# MODULIQ_PGA.net
KiCad netlist of a schematic drawn in Altium Designer
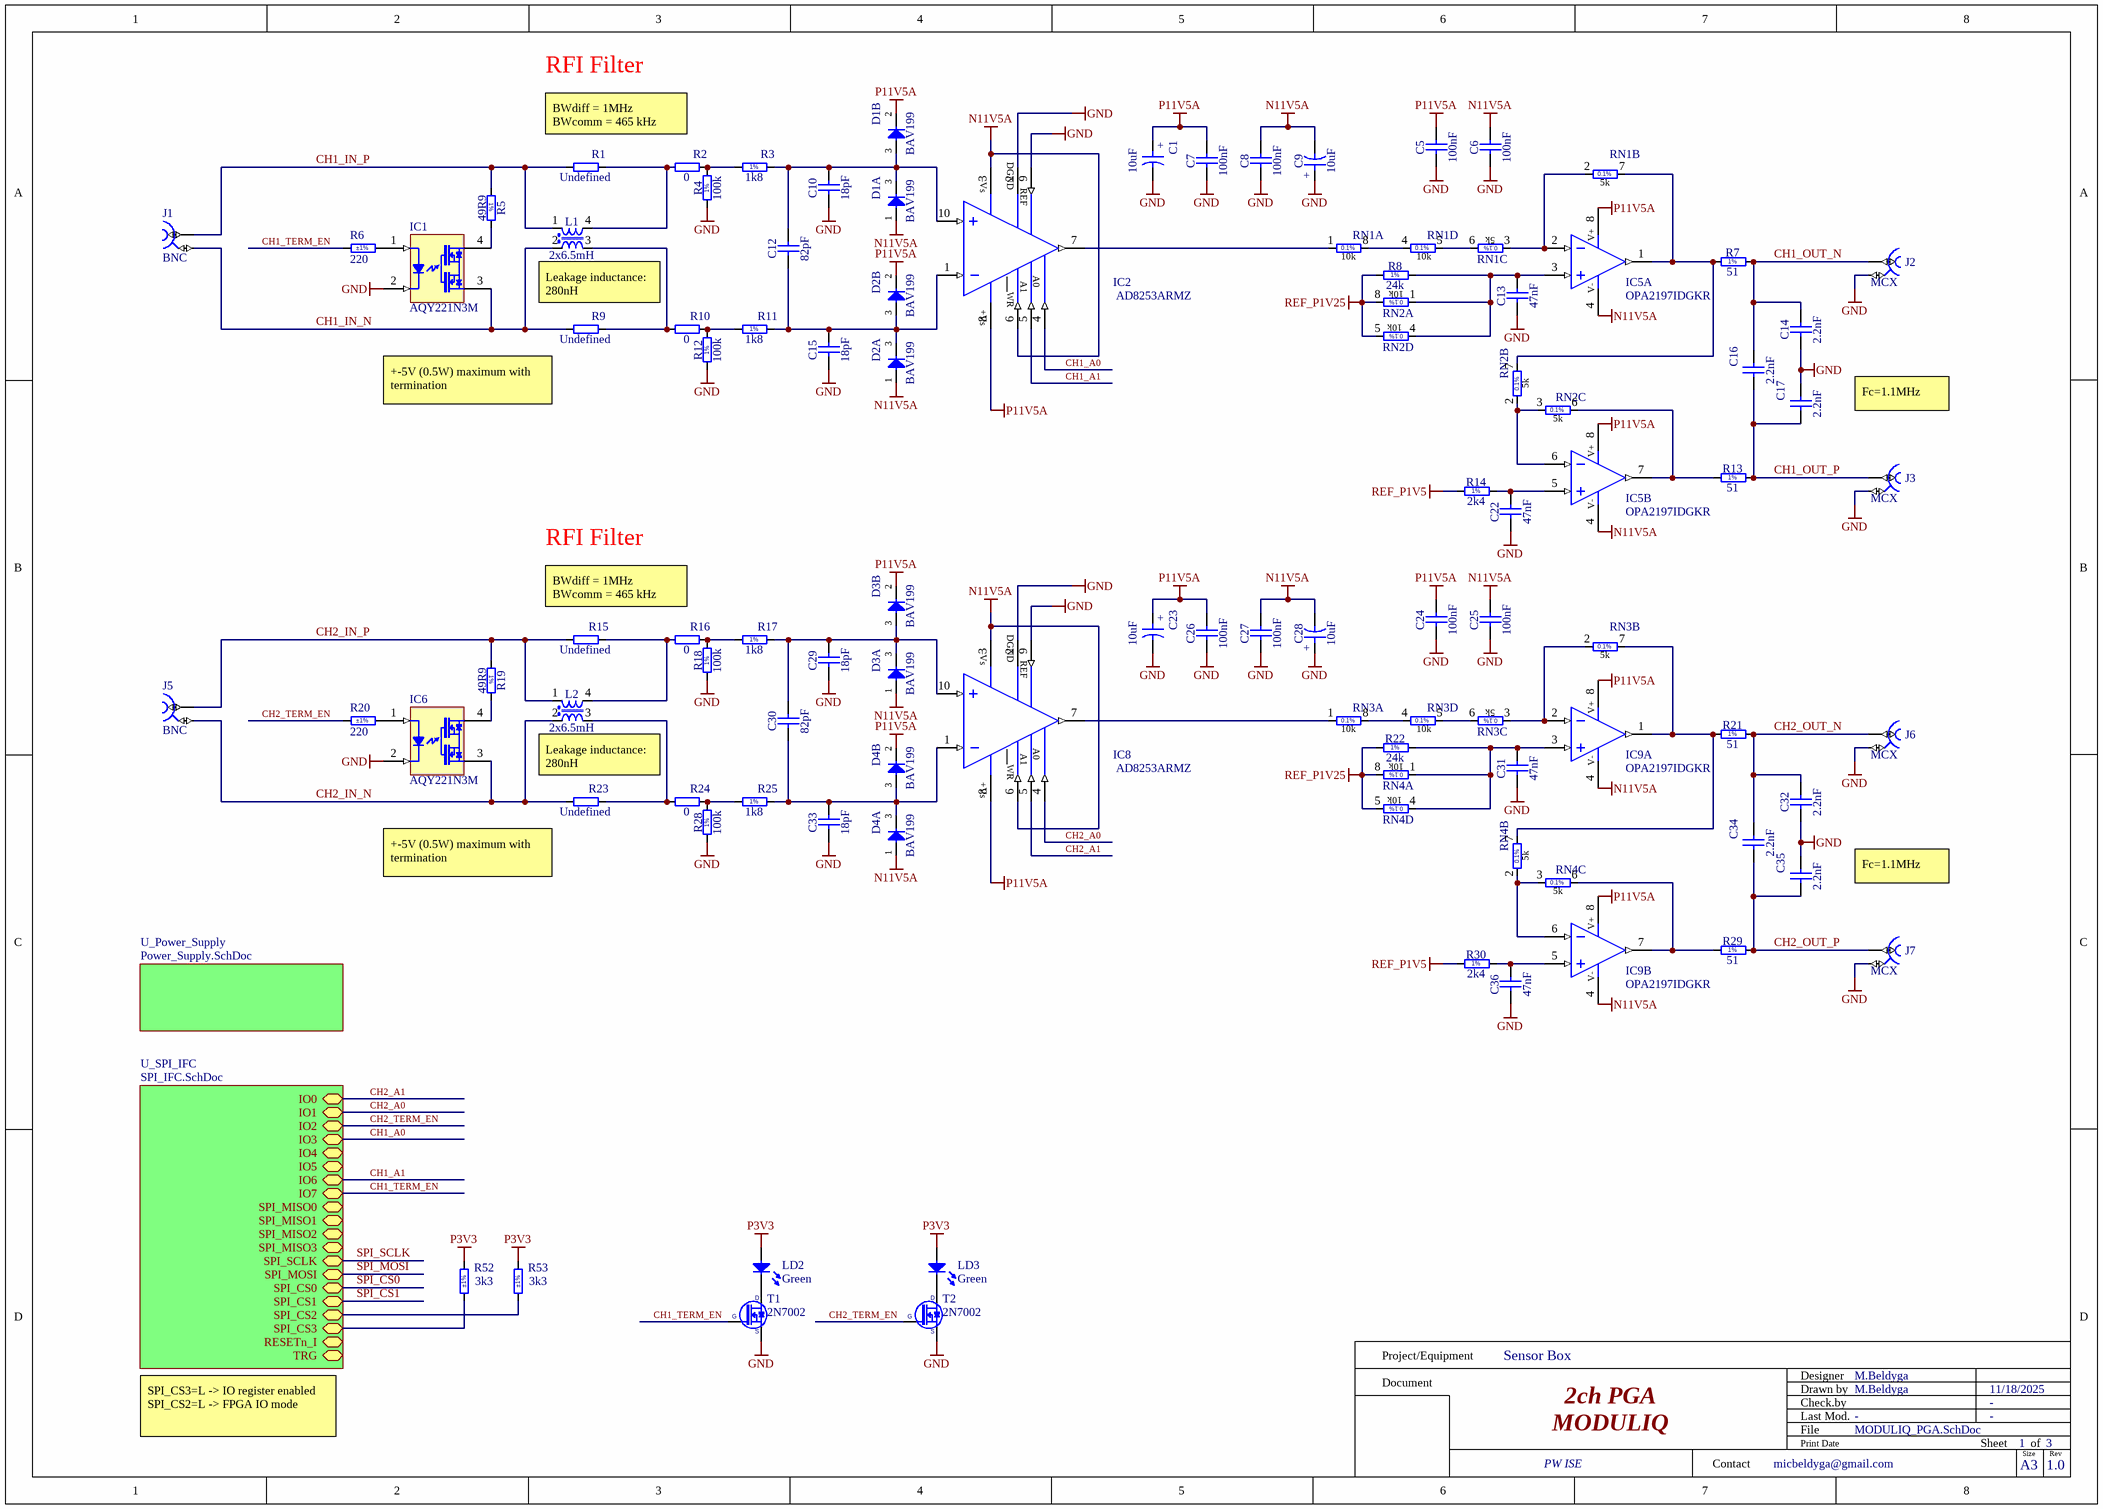
[diagram p0: MODULIQ_PGA.SchDoc]

(export (version "E")
  (design (tool "Eeschema 10.0.6"))
  (components
    (comp (ref "C1")
      (value "10uF")
      (footprint "CAPMP3216X180N")
      (description "Polarised capacitor")
      (fields
        (field (name "PART NUMBER") "CTE3216-18_10UF_16V_20%_AVX_TCJ")
        (field (name "VOLTAGE") "16V")
        (field (name "AUTHOR") "CERN DEM JLC")
      )
      (libsource (lib "Capacitors") (part "Capacitor - polarized"))
    )
    (comp (ref "C5")
      (value "100nF")
      (footprint "CAPC1005X55N")
      (description "Non-polarised capacitor")
      (fields
        (field (name "PART NUMBER") "CC0402_100NF_50V_10%_X7R")
        (field (name "VOLTAGE") "50V")
        (field (name "AUTHOR") "CERN DEM MR")
      )
      (libsource (lib "Capacitors") (part "Capacitor - non polarized"))
    )
    (comp (ref "C6")
      (value "100nF")
      (footprint "CAPC1005X55N")
      (description "Non-polarised capacitor")
      (fields
        (field (name "PART NUMBER") "CC0402_100NF_50V_10%_X7R")
        (field (name "VOLTAGE") "50V")
        (field (name "AUTHOR") "CERN DEM MR")
      )
      (libsource (lib "Capacitors") (part "Capacitor - non polarized"))
    )
    (comp (ref "C7")
      (value "100nF")
      (footprint "CAPC1005X55N")
      (description "Non-polarised capacitor")
      (fields
        (field (name "PART NUMBER") "CC0402_100NF_50V_10%_X7R")
        (field (name "VOLTAGE") "50V")
        (field (name "AUTHOR") "CERN DEM MR")
      )
      (libsource (lib "Capacitors") (part "Capacitor - non polarized"))
    )
    (comp (ref "C8")
      (value "100nF")
      (footprint "CAPC1005X55N")
      (description "Non-polarised capacitor")
      (fields
        (field (name "PART NUMBER") "CC0402_100NF_50V_10%_X7R")
        (field (name "VOLTAGE") "50V")
        (field (name "AUTHOR") "CERN DEM MR")
      )
      (libsource (lib "Capacitors") (part "Capacitor - non polarized"))
    )
    (comp (ref "C9")
      (value "10uF")
      (footprint "CAPMP3216X180N")
      (description "Polarised capacitor")
      (fields
        (field (name "PART NUMBER") "CTE3216-18_10UF_16V_20%_AVX_TCJ")
        (field (name "VOLTAGE") "16V")
        (field (name "AUTHOR") "CERN DEM JLC")
      )
      (libsource (lib "Capacitors") (part "Capacitor - polarized"))
    )
    (comp (ref "C10")
      (value "18pF")
      (footprint "CAPC1608X87N")
      (description "Non-polarised capacitor")
      (fields
        (field (name "PART NUMBER") "CC0603_18PF_50V_5%_NP0")
        (field (name "VOLTAGE") "50V")
        (field (name "AUTHOR") "CERN DEM JLC")
      )
      (libsource (lib "Capacitors") (part "Capacitor - non polarized"))
    )
    (comp (ref "C12")
      (value "82pF")
      (footprint "CAPC2012X90N")
      (description "Non-polarised capacitor")
      (fields
        (field (name "PART NUMBER") "CC0805_82PF_100V_1%_NP0_AVX_08051A820FAT2A")
        (field (name "VOLTAGE") "100V")
        (field (name "AUTHOR") "CERN DEM WB")
      )
      (libsource (lib "Capacitors") (part "Capacitor - non polarized"))
    )
    (comp (ref "C13")
      (value "47nF")
      (footprint "CAPC2012X135N")
      (description "Non-polarised capacitor")
      (fields
        (field (name "PART NUMBER") "CC0805_47NF_25V_5%_C0G")
        (field (name "VOLTAGE") "25V")
        (field (name "AUTHOR") "CERN DEM JLC")
      )
      (libsource (lib "Capacitors") (part "Capacitor - non polarized"))
    )
    (comp (ref "C14")
      (value "2.2nF")
      (footprint "CAPC2013X100N")
      (description "Non-polarised capacitor")
      (fields
        (field (name "PART NUMBER") "CC0805_2.2NF_25V_1%_C0G")
        (field (name "VOLTAGE") "25V")
        (field (name "AUTHOR") "CERN DEM JLC")
      )
      (libsource (lib "Capacitors") (part "Capacitor - non polarized"))
    )
    (comp (ref "C15")
      (value "18pF")
      (footprint "CAPC1608X87N")
      (description "Non-polarised capacitor")
      (fields
        (field (name "PART NUMBER") "CC0603_18PF_50V_5%_NP0")
        (field (name "VOLTAGE") "50V")
        (field (name "AUTHOR") "CERN DEM JLC")
      )
      (libsource (lib "Capacitors") (part "Capacitor - non polarized"))
    )
    (comp (ref "C16")
      (value "2.2nF")
      (footprint "CAPC2013X100N")
      (description "Non-polarised capacitor")
      (fields
        (field (name "PART NUMBER") "CC0805_2.2NF_25V_1%_C0G")
        (field (name "VOLTAGE") "25V")
        (field (name "AUTHOR") "CERN DEM JLC")
      )
      (libsource (lib "Capacitors") (part "Capacitor - non polarized"))
    )
    (comp (ref "C17")
      (value "2.2nF")
      (footprint "CAPC2013X100N")
      (description "Non-polarised capacitor")
      (fields
        (field (name "PART NUMBER") "CC0805_2.2NF_25V_1%_C0G")
        (field (name "VOLTAGE") "25V")
        (field (name "AUTHOR") "CERN DEM JLC")
      )
      (libsource (lib "Capacitors") (part "Capacitor - non polarized"))
    )
    (comp (ref "C22")
      (value "47nF")
      (footprint "CAPC2012X135N")
      (description "Non-polarised capacitor")
      (fields
        (field (name "PART NUMBER") "CC0805_47NF_25V_5%_C0G")
        (field (name "VOLTAGE") "25V")
        (field (name "AUTHOR") "CERN DEM JLC")
      )
      (libsource (lib "Capacitors") (part "Capacitor - non polarized"))
    )
    (comp (ref "C23")
      (value "10uF")
      (footprint "CAPMP3216X180N")
      (description "Polarised capacitor")
      (fields
        (field (name "PART NUMBER") "CTE3216-18_10UF_16V_20%_AVX_TCJ")
        (field (name "VOLTAGE") "16V")
        (field (name "AUTHOR") "CERN DEM JLC")
      )
      (libsource (lib "Capacitors") (part "Capacitor - polarized"))
    )
    (comp (ref "C24")
      (value "100nF")
      (footprint "CAPC1005X55N")
      (description "Non-polarised capacitor")
      (fields
        (field (name "PART NUMBER") "CC0402_100NF_50V_10%_X7R")
        (field (name "VOLTAGE") "50V")
        (field (name "AUTHOR") "CERN DEM MR")
      )
      (libsource (lib "Capacitors") (part "Capacitor - non polarized"))
    )
    (comp (ref "C25")
      (value "100nF")
      (footprint "CAPC1005X55N")
      (description "Non-polarised capacitor")
      (fields
        (field (name "PART NUMBER") "CC0402_100NF_50V_10%_X7R")
        (field (name "VOLTAGE") "50V")
        (field (name "AUTHOR") "CERN DEM MR")
      )
      (libsource (lib "Capacitors") (part "Capacitor - non polarized"))
    )
    (comp (ref "C26")
      (value "100nF")
      (footprint "CAPC1005X55N")
      (description "Non-polarised capacitor")
      (fields
        (field (name "PART NUMBER") "CC0402_100NF_50V_10%_X7R")
        (field (name "VOLTAGE") "50V")
        (field (name "AUTHOR") "CERN DEM MR")
      )
      (libsource (lib "Capacitors") (part "Capacitor - non polarized"))
    )
    (comp (ref "C27")
      (value "100nF")
      (footprint "CAPC1005X55N")
      (description "Non-polarised capacitor")
      (fields
        (field (name "PART NUMBER") "CC0402_100NF_50V_10%_X7R")
        (field (name "VOLTAGE") "50V")
        (field (name "AUTHOR") "CERN DEM MR")
      )
      (libsource (lib "Capacitors") (part "Capacitor - non polarized"))
    )
    (comp (ref "C28")
      (value "10uF")
      (footprint "CAPMP3216X180N")
      (description "Polarised capacitor")
      (fields
        (field (name "PART NUMBER") "CTE3216-18_10UF_16V_20%_AVX_TCJ")
        (field (name "VOLTAGE") "16V")
        (field (name "AUTHOR") "CERN DEM JLC")
      )
      (libsource (lib "Capacitors") (part "Capacitor - polarized"))
    )
    (comp (ref "C29")
      (value "18pF")
      (footprint "CAPC1608X87N")
      (description "Non-polarised capacitor")
      (fields
        (field (name "PART NUMBER") "CC0603_18PF_50V_5%_NP0")
        (field (name "VOLTAGE") "50V")
        (field (name "AUTHOR") "CERN DEM JLC")
      )
      (libsource (lib "Capacitors") (part "Capacitor - non polarized"))
    )
    (comp (ref "C30")
      (value "82pF")
      (footprint "CAPC2012X90N")
      (description "Non-polarised capacitor")
      (fields
        (field (name "PART NUMBER") "CC0805_82PF_100V_1%_NP0_AVX_08051A820FAT2A")
        (field (name "VOLTAGE") "100V")
        (field (name "AUTHOR") "CERN DEM WB")
      )
      (libsource (lib "Capacitors") (part "Capacitor - non polarized"))
    )
    (comp (ref "C31")
      (value "47nF")
      (footprint "CAPC2012X135N")
      (description "Non-polarised capacitor")
      (fields
        (field (name "PART NUMBER") "CC0805_47NF_25V_5%_C0G")
        (field (name "VOLTAGE") "25V")
        (field (name "AUTHOR") "CERN DEM JLC")
      )
      (libsource (lib "Capacitors") (part "Capacitor - non polarized"))
    )
    (comp (ref "C32")
      (value "2.2nF")
      (footprint "CAPC2013X100N")
      (description "Non-polarised capacitor")
      (fields
        (field (name "PART NUMBER") "CC0805_2.2NF_25V_1%_C0G")
        (field (name "VOLTAGE") "25V")
        (field (name "AUTHOR") "CERN DEM JLC")
      )
      (libsource (lib "Capacitors") (part "Capacitor - non polarized"))
    )
    (comp (ref "C33")
      (value "18pF")
      (footprint "CAPC1608X87N")
      (description "Non-polarised capacitor")
      (fields
        (field (name "PART NUMBER") "CC0603_18PF_50V_5%_NP0")
        (field (name "VOLTAGE") "50V")
        (field (name "AUTHOR") "CERN DEM JLC")
      )
      (libsource (lib "Capacitors") (part "Capacitor - non polarized"))
    )
    (comp (ref "C34")
      (value "2.2nF")
      (footprint "CAPC2013X100N")
      (description "Non-polarised capacitor")
      (fields
        (field (name "PART NUMBER") "CC0805_2.2NF_25V_1%_C0G")
        (field (name "VOLTAGE") "25V")
        (field (name "AUTHOR") "CERN DEM JLC")
      )
      (libsource (lib "Capacitors") (part "Capacitor - non polarized"))
    )
    (comp (ref "C35")
      (value "2.2nF")
      (footprint "CAPC2013X100N")
      (description "Non-polarised capacitor")
      (fields
        (field (name "PART NUMBER") "CC0805_2.2NF_25V_1%_C0G")
        (field (name "VOLTAGE") "25V")
        (field (name "AUTHOR") "CERN DEM JLC")
      )
      (libsource (lib "Capacitors") (part "Capacitor - non polarized"))
    )
    (comp (ref "C36")
      (value "47nF")
      (footprint "CAPC2012X135N")
      (description "Non-polarised capacitor")
      (fields
        (field (name "PART NUMBER") "CC0805_47NF_25V_5%_C0G")
        (field (name "VOLTAGE") "25V")
        (field (name "AUTHOR") "CERN DEM JLC")
      )
      (libsource (lib "Capacitors") (part "Capacitor - non polarized"))
    )
    (comp (ref "D1")
      (value "BAV199")
      (footprint "SOT95P240X110-3N")
      (description "Serial Diode")
      (fields
        (field (name "VOLTAGE") "75V")
        (field (name "POWER") "250mW")
        (field (name "AUTHOR") "CERN DEM JMW")
      )
      (libsource (lib "ICs And Semiconductors") (part "Diode x2 A1C3_A3C2"))
    )
    (comp (ref "D2")
      (value "BAV199")
      (footprint "SOT95P240X110-3N")
      (description "Serial Diode")
      (fields
        (field (name "VOLTAGE") "75V")
        (field (name "POWER") "250mW")
        (field (name "AUTHOR") "CERN DEM JMW")
      )
      (libsource (lib "ICs And Semiconductors") (part "Diode x2 A1C3_A3C2"))
    )
    (comp (ref "D3")
      (value "BAV199")
      (footprint "SOT95P240X110-3N")
      (description "Serial Diode")
      (fields
        (field (name "VOLTAGE") "75V")
        (field (name "POWER") "250mW")
        (field (name "AUTHOR") "CERN DEM JMW")
      )
      (libsource (lib "ICs And Semiconductors") (part "Diode x2 A1C3_A3C2"))
    )
    (comp (ref "D4")
      (value "BAV199")
      (footprint "SOT95P240X110-3N")
      (description "Serial Diode")
      (fields
        (field (name "VOLTAGE") "75V")
        (field (name "POWER") "250mW")
        (field (name "AUTHOR") "CERN DEM JMW")
      )
      (libsource (lib "ICs And Semiconductors") (part "Diode x2 A1C3_A3C2"))
    )
    (comp (ref "IC1")
      (value "AQY221N3M")
      (footprint "PANASONIC_AQY22(SON)")
      (description "PhotoMOS Relay")
      (fields (field (name "MANUFACTURER") "PANASONIC") (field (name "AUTHOR") "CERN DEM JLC"))
      (libsource (lib "ICs And Semiconductors") (part "PhotoMOS Relay x1 Type5_a"))
    )
    (comp (ref "IC2")
      (value "AD8253ARMZ")
      (footprint "SOP50P490X110-10N")
      (description "10MHz, 20V/us, G= 1, 10, 100, 1000 iCMOS Programmable Gain Instrumentation Amplifier")
      (fields (field (name "MANUFACTURER") "ANALOG DEVICES") (field (name "AUTHOR") "CERN DEM JLC"))
      (libsource (lib "ICs And Semiconductors") (part "AD8253"))
    )
    (comp (ref "IC5")
      (value "OPA2197IDGKR")
      (footprint "SOP65P490X110-8N")
      (description "36-V, Precision, Rail-to-Rail Input Output, Low Offset Voltage Op Amp 8-VSSOP")
      (fields (field (name "MANUFACTURER") "TEXAS INSTRUMENTS") (field (name "AUTHOR") "GK"))
      (libsource (lib "LIBRARY_SCH") (part "OA_OPA2197IDGKR"))
    )
    (comp (ref "IC6")
      (value "AQY221N3M")
      (footprint "PANASONIC_AQY22(SON)")
      (description "PhotoMOS Relay")
      (fields (field (name "MANUFACTURER") "PANASONIC") (field (name "AUTHOR") "CERN DEM JLC"))
      (libsource (lib "ICs And Semiconductors") (part "PhotoMOS Relay x1 Type5_a"))
    )
    (comp (ref "IC8")
      (value "AD8253ARMZ")
      (footprint "SOP50P490X110-10N")
      (description "10MHz, 20V/us, G= 1, 10, 100, 1000 iCMOS Programmable Gain Instrumentation Amplifier")
      (fields (field (name "MANUFACTURER") "ANALOG DEVICES") (field (name "AUTHOR") "CERN DEM JLC"))
      (libsource (lib "ICs And Semiconductors") (part "AD8253"))
    )
    (comp (ref "IC9")
      (value "OPA2197IDGKR")
      (footprint "SOP65P490X110-8N")
      (description "36-V, Precision, Rail-to-Rail Input Output, Low Offset Voltage Op Amp 8-VSSOP")
      (fields (field (name "MANUFACTURER") "TEXAS INSTRUMENTS") (field (name "AUTHOR") "GK"))
      (libsource (lib "LIBRARY_SCH") (part "OA_OPA2197IDGKR"))
    )
    (comp (ref "J1")
      (value "BNC")
      (footprint "AMPHENOL_112515")
      (fields
        (field (name "PART NUMBER") "AMPHENOL_112515")
        (field (name "MANUFACTURER") "AMPHENOL-RF")
        (field (name "MANUFACTURER PART NUMBER") "112515")
        (field (name "AUTHOR") "CERN DEM HF")
      )
      (libsource (lib "Connectors") (part "Coax_1Female_1Shield"))
    )
    (comp (ref "J2")
      (value "MCX")
      (footprint "AMPHENOL_919-109J-51PX")
      (fields
        (field (name "PART NUMBER") "AMPHENOL_919-109J-51PX")
        (field (name "MANUFACTURER") "AMPHENOL")
        (field (name "MANUFACTURER PART NUMBER") "919-109J-51PX (MCX6251B1-3GT30G-50)")
        (field (name "AUTHOR") "CERN DEM BC")
      )
      (libsource (lib "") (part "Coax_1Female_1Shield_1"))
    )
    (comp (ref "J3")
      (value "MCX")
      (footprint "AMPHENOL_919-109J-51PX")
      (fields
        (field (name "PART NUMBER") "AMPHENOL_919-109J-51PX")
        (field (name "MANUFACTURER") "AMPHENOL")
        (field (name "MANUFACTURER PART NUMBER") "919-109J-51PX (MCX6251B1-3GT30G-50)")
        (field (name "AUTHOR") "CERN DEM BC")
      )
      (libsource (lib "") (part "Coax_1Female_1Shield_1"))
    )
    (comp (ref "J5")
      (value "BNC")
      (footprint "AMPHENOL_112515")
      (fields
        (field (name "PART NUMBER") "AMPHENOL_112515")
        (field (name "MANUFACTURER") "AMPHENOL-RF")
        (field (name "MANUFACTURER PART NUMBER") "112515")
        (field (name "AUTHOR") "CERN DEM HF")
      )
      (libsource (lib "Connectors") (part "Coax_1Female_1Shield"))
    )
    (comp (ref "J6")
      (value "MCX")
      (footprint "AMPHENOL_919-109J-51PX")
      (fields
        (field (name "PART NUMBER") "AMPHENOL_919-109J-51PX")
        (field (name "MANUFACTURER") "AMPHENOL")
        (field (name "MANUFACTURER PART NUMBER") "919-109J-51PX (MCX6251B1-3GT30G-50)")
        (field (name "AUTHOR") "CERN DEM BC")
      )
      (libsource (lib "") (part "Coax_1Female_1Shield_1"))
    )
    (comp (ref "J7")
      (value "MCX")
      (footprint "AMPHENOL_919-109J-51PX")
      (fields
        (field (name "PART NUMBER") "AMPHENOL_919-109J-51PX")
        (field (name "MANUFACTURER") "AMPHENOL")
        (field (name "MANUFACTURER PART NUMBER") "919-109J-51PX (MCX6251B1-3GT30G-50)")
        (field (name "AUTHOR") "CERN DEM BC")
      )
      (libsource (lib "") (part "Coax_1Female_1Shield_1"))
    )
    (comp (ref "L1")
      (value "2x6.5mH")
      (footprint "IND_WURTH_WE-SL2")
      (description "Inductor Common Mode")
      (fields
        (field (name "PART NUMBER") "IND_6.5MH_50%_WURTH_WE-SL2-744229")
        (field (name "POWER") "400mA")
        (field (name "AUTHOR") "CERN DEM JLC")
      )
      (libsource (lib "Inductors & Transformers") (part "Inductor Common Mode 1Dot-4 2Dot-3"))
    )
    (comp (ref "L2")
      (value "2x6.5mH")
      (footprint "IND_WURTH_WE-SL2")
      (description "Inductor Common Mode")
      (fields
        (field (name "PART NUMBER") "IND_6.5MH_50%_WURTH_WE-SL2-744229")
        (field (name "POWER") "400mA")
        (field (name "AUTHOR") "CERN DEM JLC")
      )
      (libsource (lib "Inductors & Transformers") (part "Inductor Common Mode 1Dot-4 2Dot-3"))
    )
    (comp (ref "LD2")
      (value "Green")
      (footprint "LED_KINGBRIGHT_KP-1608CGCK")
      (description "LED Green 1C 2A")
      (fields
        (field (name "PART NUMBER") "LED_KINGBRIGHT_KP-1608CGCK")
        (field (name "MANUFACTURER") "KINGBRIGHT")
        (field (name "AUTHOR") "CERN DEM HF")
      )
      (libsource (lib "ICs And Semiconductors") (part "LED Green 1C 2A"))
    )
    (comp (ref "LD3")
      (value "Green")
      (footprint "LED_KINGBRIGHT_KP-1608CGCK")
      (description "LED Green 1C 2A")
      (fields
        (field (name "PART NUMBER") "LED_KINGBRIGHT_KP-1608CGCK")
        (field (name "MANUFACTURER") "KINGBRIGHT")
        (field (name "AUTHOR") "CERN DEM HF")
      )
      (libsource (lib "ICs And Semiconductors") (part "LED Green 1C 2A"))
    )
    (comp (ref "R1")
      (value "Undefined")
      (footprint "RESC1608X55N")
      (description "Resistor")
      (fields (field (name "PART NUMBER") "R0603_NO-VALUE") (field (name "AUTHOR") "CERN DEM JLC"))
      (libsource (lib "Resistors") (part "Resistor"))
    )
    (comp (ref "R2")
      (value "0")
      (footprint "RESC1608X55N")
      (description "Resistor")
      (fields
        (field (name "PART NUMBER") "R0603_0R_JUMPER")
        (field (name "MANUFACTURER") "GENERIC")
        (field (name "AUTHOR") "CERN DEM JLC")
      )
      (libsource (lib "Resistors") (part "Resistor"))
    )
    (comp (ref "R3")
      (value "1k8")
      (footprint "RESC1608X55N")
      (description "Resistor - 1%")
      (fields
        (field (name "PART NUMBER") "R0603_1K8_1%_0.1W_100PPM")
        (field (name "POWER") "0.1W")
        (field (name "AUTHOR") "CERN DEM JLC")
      )
      (libsource (lib "") (part "Resistor - 1%_1"))
    )
    (comp (ref "R4")
      (value "100k")
      (footprint "RESC1608X55N")
      (description "Resistor - 1%")
      (fields
        (field (name "PART NUMBER") "R0603_100K_1%_0.1W_100PPM")
        (field (name "POWER") "0.1W")
        (field (name "AUTHOR") "CERN DEM JLC")
      )
      (libsource (lib "") (part "Resistor - 1%_1"))
    )
    (comp (ref "R5")
      (value "49R9")
      (footprint "RESC6331X70N")
      (description "Resistor - 1%")
      (fields
        (field (name "PART NUMBER") "R2512_49R9_1%_1W_100PPM_VISHAY_CRCW")
        (field (name "POWER") "1W")
        (field (name "AUTHOR") "CERN DEM JLC")
      )
      (libsource (lib "") (part "Resistor - 1%_1"))
    )
    (comp (ref "R6")
      (value "220")
      (footprint "RESC1005X40N")
      (description "Resistor - 1%")
      (fields
        (field (name "TOLERANCE") "±1%")
        (field (name "PART NUMBER") "R0402_220R_1%_0.0625W_100PPM")
        (field (name "POWER") "0.0625W")
        (field (name "AUTHOR") "CERN DEM JLC")
      )
      (libsource (lib "Resistors") (part "Resistor - 1%"))
    )
    (comp (ref "R7")
      (value "51")
      (footprint "RESC1005X40N")
      (description "Resistor - 1%")
      (fields
        (field (name "PART NUMBER") "R0402_51R_1%_0.0625W_100PPM")
        (field (name "POWER") "0.0625W")
        (field (name "AUTHOR") "CERN DEM JLC")
      )
      (libsource (lib "Resistors") (part "Resistor - 1%"))
    )
    (comp (ref "R8")
      (value "24k")
      (footprint "RESC1608X55N")
      (description "Resistor - 1%")
      (fields
        (field (name "PART NUMBER") "R0603_24K_1%_0.1W_100PPM")
        (field (name "POWER") "0.1W")
        (field (name "AUTHOR") "CERN DEM JLC")
      )
      (libsource (lib "") (part "Resistor - 1%_1"))
    )
    (comp (ref "R9")
      (value "Undefined")
      (footprint "RESC1608X55N")
      (description "Resistor")
      (fields (field (name "PART NUMBER") "R0603_NO-VALUE") (field (name "AUTHOR") "CERN DEM JLC"))
      (libsource (lib "Resistors") (part "Resistor"))
    )
    (comp (ref "R10")
      (value "0")
      (footprint "RESC1608X55N")
      (description "Resistor")
      (fields
        (field (name "PART NUMBER") "R0603_0R_JUMPER")
        (field (name "MANUFACTURER") "GENERIC")
        (field (name "AUTHOR") "CERN DEM JLC")
      )
      (libsource (lib "Resistors") (part "Resistor"))
    )
    (comp (ref "R11")
      (value "1k8")
      (footprint "RESC1608X55N")
      (description "Resistor - 1%")
      (fields
        (field (name "PART NUMBER") "R0603_1K8_1%_0.1W_100PPM")
        (field (name "POWER") "0.1W")
        (field (name "AUTHOR") "CERN DEM JLC")
      )
      (libsource (lib "") (part "Resistor - 1%_1"))
    )
    (comp (ref "R12")
      (value "100k")
      (footprint "RESC1608X55N")
      (description "Resistor - 1%")
      (fields
        (field (name "PART NUMBER") "R0603_100K_1%_0.1W_100PPM")
        (field (name "POWER") "0.1W")
        (field (name "AUTHOR") "CERN DEM JLC")
      )
      (libsource (lib "") (part "Resistor - 1%_1"))
    )
    (comp (ref "R13")
      (value "51")
      (footprint "RESC1005X40N")
      (description "Resistor - 1%")
      (fields
        (field (name "PART NUMBER") "R0402_51R_1%_0.0625W_100PPM")
        (field (name "POWER") "0.0625W")
        (field (name "AUTHOR") "CERN DEM JLC")
      )
      (libsource (lib "Resistors") (part "Resistor - 1%"))
    )
    (comp (ref "R14")
      (value "2k4")
      (footprint "RESC1005X40N")
      (description "Resistor - 1%")
      (fields
        (field (name "PART NUMBER") "R0402_2K4_1%_0.0625W_100PPM")
        (field (name "POWER") "0.0625W")
        (field (name "AUTHOR") "CERN DEM JLC")
      )
      (libsource (lib "Resistors") (part "Resistor - 1%"))
    )
    (comp (ref "R15")
      (value "Undefined")
      (footprint "RESC1608X55N")
      (description "Resistor")
      (fields (field (name "PART NUMBER") "R0603_NO-VALUE") (field (name "AUTHOR") "CERN DEM JLC"))
      (libsource (lib "Resistors") (part "Resistor"))
    )
    (comp (ref "R16")
      (value "0")
      (footprint "RESC1608X55N")
      (description "Resistor")
      (fields
        (field (name "PART NUMBER") "R0603_0R_JUMPER")
        (field (name "MANUFACTURER") "GENERIC")
        (field (name "AUTHOR") "CERN DEM JLC")
      )
      (libsource (lib "Resistors") (part "Resistor"))
    )
    (comp (ref "R17")
      (value "1k8")
      (footprint "RESC1608X55N")
      (description "Resistor - 1%")
      (fields
        (field (name "PART NUMBER") "R0603_1K8_1%_0.1W_100PPM")
        (field (name "POWER") "0.1W")
        (field (name "AUTHOR") "CERN DEM JLC")
      )
      (libsource (lib "") (part "Resistor - 1%_1"))
    )
    (comp (ref "R18")
      (value "100k")
      (footprint "RESC1608X55N")
      (description "Resistor - 1%")
      (fields
        (field (name "PART NUMBER") "R0603_100K_1%_0.1W_100PPM")
        (field (name "POWER") "0.1W")
        (field (name "AUTHOR") "CERN DEM JLC")
      )
      (libsource (lib "") (part "Resistor - 1%_1"))
    )
    (comp (ref "R19")
      (value "49R9")
      (footprint "RESC6331X70N")
      (description "Resistor - 1%")
      (fields
        (field (name "PART NUMBER") "R2512_49R9_1%_1W_100PPM_VISHAY_CRCW")
        (field (name "POWER") "1W")
        (field (name "AUTHOR") "CERN DEM JLC")
      )
      (libsource (lib "") (part "Resistor - 1%_1"))
    )
    (comp (ref "R20")
      (value "220")
      (footprint "RESC1005X40N")
      (description "Resistor - 1%")
      (fields
        (field (name "TOLERANCE") "±1%")
        (field (name "PART NUMBER") "R0402_220R_1%_0.0625W_100PPM")
        (field (name "POWER") "0.0625W")
        (field (name "AUTHOR") "CERN DEM JLC")
      )
      (libsource (lib "Resistors") (part "Resistor - 1%"))
    )
    (comp (ref "R21")
      (value "51")
      (footprint "RESC1005X40N")
      (description "Resistor - 1%")
      (fields
        (field (name "PART NUMBER") "R0402_51R_1%_0.0625W_100PPM")
        (field (name "POWER") "0.0625W")
        (field (name "AUTHOR") "CERN DEM JLC")
      )
      (libsource (lib "Resistors") (part "Resistor - 1%"))
    )
    (comp (ref "R22")
      (value "24k")
      (footprint "RESC1608X55N")
      (description "Resistor - 1%")
      (fields
        (field (name "PART NUMBER") "R0603_24K_1%_0.1W_100PPM")
        (field (name "POWER") "0.1W")
        (field (name "AUTHOR") "CERN DEM JLC")
      )
      (libsource (lib "") (part "Resistor - 1%_1"))
    )
    (comp (ref "R23")
      (value "Undefined")
      (footprint "RESC1608X55N")
      (description "Resistor")
      (fields (field (name "PART NUMBER") "R0603_NO-VALUE") (field (name "AUTHOR") "CERN DEM JLC"))
      (libsource (lib "Resistors") (part "Resistor"))
    )
    (comp (ref "R24")
      (value "0")
      (footprint "RESC1608X55N")
      (description "Resistor")
      (fields
        (field (name "PART NUMBER") "R0603_0R_JUMPER")
        (field (name "MANUFACTURER") "GENERIC")
        (field (name "AUTHOR") "CERN DEM JLC")
      )
      (libsource (lib "Resistors") (part "Resistor"))
    )
    (comp (ref "R25")
      (value "1k8")
      (footprint "RESC1608X55N")
      (description "Resistor - 1%")
      (fields
        (field (name "PART NUMBER") "R0603_1K8_1%_0.1W_100PPM")
        (field (name "POWER") "0.1W")
        (field (name "AUTHOR") "CERN DEM JLC")
      )
      (libsource (lib "") (part "Resistor - 1%_1"))
    )
    (comp (ref "R28")
      (value "100k")
      (footprint "RESC1608X55N")
      (description "Resistor - 1%")
      (fields
        (field (name "PART NUMBER") "R0603_100K_1%_0.1W_100PPM")
        (field (name "POWER") "0.1W")
        (field (name "AUTHOR") "CERN DEM JLC")
      )
      (libsource (lib "") (part "Resistor - 1%_1"))
    )
    (comp (ref "R29")
      (value "51")
      (footprint "RESC1005X40N")
      (description "Resistor - 1%")
      (fields
        (field (name "PART NUMBER") "R0402_51R_1%_0.0625W_100PPM")
        (field (name "POWER") "0.0625W")
        (field (name "AUTHOR") "CERN DEM JLC")
      )
      (libsource (lib "Resistors") (part "Resistor - 1%"))
    )
    (comp (ref "R30")
      (value "2k4")
      (footprint "RESC1005X40N")
      (description "Resistor - 1%")
      (fields
        (field (name "PART NUMBER") "R0402_2K4_1%_0.0625W_100PPM")
        (field (name "POWER") "0.0625W")
        (field (name "AUTHOR") "CERN DEM JLC")
      )
      (libsource (lib "Resistors") (part "Resistor - 1%"))
    )
    (comp (ref "R52")
      (value "3k3")
      (footprint "RESC1005X40N")
      (description "Resistor - 1%")
      (fields
        (field (name "TOLERANCE") "±1%")
        (field (name "PART NUMBER") "R0402_3K3_1%_0.0625W_100PPM")
        (field (name "POWER") "0.0625W")
        (field (name "AUTHOR") "CERN DEM JLC")
      )
      (libsource (lib "Resistors") (part "Resistor - 1%"))
    )
    (comp (ref "R53")
      (value "3k3")
      (footprint "RESC1005X40N")
      (description "Resistor - 1%")
      (fields
        (field (name "TOLERANCE") "±1%")
        (field (name "PART NUMBER") "R0402_3K3_1%_0.0625W_100PPM")
        (field (name "POWER") "0.0625W")
        (field (name "AUTHOR") "CERN DEM JLC")
      )
      (libsource (lib "Resistors") (part "Resistor - 1%"))
    )
    (comp (ref "RN1")
      (value "10k 5K 5K 10K")
      (footprint "SOIC127P600X175-8N")
      (description "DIL8 Resistor Network 4 Resistors 10k-5k-5k-10k 0.1%")
      (fields
        (field (name "PART NUMBER") "RN_10K_5K_VISHAY_AORN2-1AT3")
        (field (name "POWER") "4x0.1W")
        (field (name "AUTHOR") "CERN DEM JLC")
      )
      (libsource (lib "Resistors") (part "RN DIL8_4xR_10k-5k-5k-10k_0.1%"))
    )
    (comp (ref "RN2")
      (value "10k 5K 5K 10K")
      (footprint "SOIC127P600X175-8N")
      (description "DIL8 Resistor Network 4 Resistors 10k-5k-5k-10k 0.1%")
      (fields
        (field (name "PART NUMBER") "RN_10K_5K_VISHAY_AORN2-1AT3")
        (field (name "POWER") "4x0.1W")
        (field (name "AUTHOR") "CERN DEM JLC")
      )
      (libsource (lib "Resistors") (part "RN DIL8_4xR_10k-5k-5k-10k_0.1%"))
    )
    (comp (ref "RN3")
      (value "10k 5K 5K 10K")
      (footprint "SOIC127P600X175-8N")
      (description "DIL8 Resistor Network 4 Resistors 10k-5k-5k-10k 0.1%")
      (fields
        (field (name "PART NUMBER") "RN_10K_5K_VISHAY_AORN2-1AT3")
        (field (name "POWER") "4x0.1W")
        (field (name "AUTHOR") "CERN DEM JLC")
      )
      (libsource (lib "Resistors") (part "RN DIL8_4xR_10k-5k-5k-10k_0.1%"))
    )
    (comp (ref "RN4")
      (value "10k 5K 5K 10K")
      (footprint "SOIC127P600X175-8N")
      (description "DIL8 Resistor Network 4 Resistors 10k-5k-5k-10k 0.1%")
      (fields
        (field (name "PART NUMBER") "RN_10K_5K_VISHAY_AORN2-1AT3")
        (field (name "POWER") "4x0.1W")
        (field (name "AUTHOR") "CERN DEM JLC")
      )
      (libsource (lib "Resistors") (part "RN DIL8_4xR_10k-5k-5k-10k_0.1%"))
    )
    (comp (ref "T1")
      (value "2N7002")
      (footprint "SOT95P240X130-3N")
      (description "N-CHANNEL MOSFET WITH DIODE")
      (fields (field (name "MANUFACTURER") "FAIRCHILD SEMICONDUCTOR") (field (name "AUTHOR") "CERN DEM JLC"))
      (libsource (lib "ICs And Semiconductors") (part "N-MOSFET-D 1G 2S 3D"))
    )
    (comp (ref "T2")
      (value "2N7002")
      (footprint "SOT95P240X130-3N")
      (description "N-CHANNEL MOSFET WITH DIODE")
      (fields (field (name "MANUFACTURER") "FAIRCHILD SEMICONDUCTOR") (field (name "AUTHOR") "CERN DEM JLC"))
      (libsource (lib "ICs And Semiconductors") (part "N-MOSFET-D 1G 2S 3D"))
    )
  )
  (nets
    (net (code "1") (name "/CH1_A0") (class "Default")
      (node (ref "IC2") (pin "4") (pinfunction "A0_4") (pintype "input"))
    )
    (net (code "2") (name "/CH1_A1") (class "Default")
      (node (ref "IC2") (pin "5") (pinfunction "A1_5") (pintype "input"))
    )
    (net (code "3") (name "/CH1_IN_N") (class "Default")
      (node (ref "IC1") (pin "3") (pinfunction "C_3") (pintype "open_collector"))
      (node (ref "J1") (pin "2") (pinfunction "2_2") (pintype "bidirectional"))
      (node (ref "L1") (pin "2") (pinfunction "2_2") (pintype "passive"))
      (node (ref "R9") (pin "1") (pinfunction "1_1") (pintype "passive"))
    )
    (net (code "4") (name "/CH1_IN_P") (class "Default")
      (node (ref "J1") (pin "1") (pinfunction "1_1") (pintype "bidirectional"))
      (node (ref "L1") (pin "1") (pinfunction "1_1") (pintype "passive"))
      (node (ref "R1") (pin "1") (pinfunction "1_1") (pintype "passive"))
      (node (ref "R5") (pin "1") (pinfunction "1_1") (pintype "passive"))
    )
    (net (code "5") (name "/CH1_OUT_N") (class "Default")
      (node (ref "C14") (pin "2") (pinfunction "2_2") (pintype "passive"))
      (node (ref "C16") (pin "2") (pinfunction "2_2") (pintype "passive"))
      (node (ref "J2") (pin "1") (pinfunction "1_1") (pintype "bidirectional"))
      (node (ref "R7") (pin "2") (pinfunction "2_2") (pintype "passive"))
    )
    (net (code "6") (name "/CH1_OUT_P") (class "Default")
      (node (ref "C16") (pin "1") (pinfunction "1_1") (pintype "passive"))
      (node (ref "C17") (pin "1") (pinfunction "1_1") (pintype "passive"))
      (node (ref "J3") (pin "1") (pinfunction "1_1") (pintype "bidirectional"))
      (node (ref "R13") (pin "2") (pinfunction "2_2") (pintype "passive"))
    )
    (net (code "7") (name "/CH1_TERM_EN") (class "Default")
      (node (ref "R6") (pin "1") (pinfunction "1_1") (pintype "passive"))
      (node (ref "T1") (pin "1") (pinfunction "G_1") (pintype "passive"))
    )
    (net (code "8") (name "/CH2_A0") (class "Default")
      (node (ref "IC8") (pin "4") (pinfunction "A0_4") (pintype "input"))
    )
    (net (code "9") (name "/CH2_A1") (class "Default")
      (node (ref "IC8") (pin "5") (pinfunction "A1_5") (pintype "input"))
    )
    (net (code "10") (name "/CH2_IN_N") (class "Default")
      (node (ref "IC6") (pin "3") (pinfunction "C_3") (pintype "open_collector"))
      (node (ref "J5") (pin "2") (pinfunction "2_2") (pintype "bidirectional"))
      (node (ref "L2") (pin "2") (pinfunction "2_2") (pintype "passive"))
      (node (ref "R23") (pin "1") (pinfunction "1_1") (pintype "passive"))
    )
    (net (code "11") (name "/CH2_IN_P") (class "Default")
      (node (ref "J5") (pin "1") (pinfunction "1_1") (pintype "bidirectional"))
      (node (ref "L2") (pin "1") (pinfunction "1_1") (pintype "passive"))
      (node (ref "R15") (pin "1") (pinfunction "1_1") (pintype "passive"))
      (node (ref "R19") (pin "1") (pinfunction "1_1") (pintype "passive"))
    )
    (net (code "12") (name "/CH2_OUT_N") (class "Default")
      (node (ref "C32") (pin "2") (pinfunction "2_2") (pintype "passive"))
      (node (ref "C34") (pin "2") (pinfunction "2_2") (pintype "passive"))
      (node (ref "J6") (pin "1") (pinfunction "1_1") (pintype "bidirectional"))
      (node (ref "R21") (pin "2") (pinfunction "2_2") (pintype "passive"))
    )
    (net (code "13") (name "/CH2_OUT_P") (class "Default")
      (node (ref "C34") (pin "1") (pinfunction "1_1") (pintype "passive"))
      (node (ref "C35") (pin "1") (pinfunction "1_1") (pintype "passive"))
      (node (ref "J7") (pin "1") (pinfunction "1_1") (pintype "bidirectional"))
      (node (ref "R29") (pin "2") (pinfunction "2_2") (pintype "passive"))
    )
    (net (code "14") (name "/CH2_TERM_EN") (class "Default")
      (node (ref "R20") (pin "1") (pinfunction "1_1") (pintype "passive"))
      (node (ref "T2") (pin "1") (pinfunction "G_1") (pintype "passive"))
    )
    (net (code "20") (name "/SPI_CS2") (class "Default")
      (node (ref "R53") (pin "2") (pinfunction "2_2") (pintype "passive"))
    )
    (net (code "21") (name "/SPI_CS3") (class "Default")
      (node (ref "R52") (pin "2") (pinfunction "2_2") (pintype "passive"))
    )
    (net (code "29") (name "GND") (class "Default")
      (node (ref "C1") (pin "2") (pinfunction "2_2") (pintype "passive"))
      (node (ref "C10") (pin "1") (pinfunction "1_1") (pintype "passive"))
      (node (ref "C13") (pin "1") (pinfunction "1_1") (pintype "passive"))
      (node (ref "C14") (pin "1") (pinfunction "1_1") (pintype "passive"))
      (node (ref "C15") (pin "1") (pinfunction "1_1") (pintype "passive"))
      (node (ref "C17") (pin "2") (pinfunction "2_2") (pintype "passive"))
      (node (ref "C22") (pin "1") (pinfunction "1_1") (pintype "passive"))
      (node (ref "C23") (pin "2") (pinfunction "2_2") (pintype "passive"))
      (node (ref "C24") (pin "1") (pinfunction "1_1") (pintype "passive"))
      (node (ref "C25") (pin "1") (pinfunction "1_1") (pintype "passive"))
      (node (ref "C26") (pin "1") (pinfunction "1_1") (pintype "passive"))
      (node (ref "C27") (pin "1") (pinfunction "1_1") (pintype "passive"))
      (node (ref "C28") (pin "1") (pinfunction "1_1") (pintype "passive"))
      (node (ref "C29") (pin "1") (pinfunction "1_1") (pintype "passive"))
      (node (ref "C31") (pin "1") (pinfunction "1_1") (pintype "passive"))
      (node (ref "C32") (pin "1") (pinfunction "1_1") (pintype "passive"))
      (node (ref "C33") (pin "1") (pinfunction "1_1") (pintype "passive"))
      (node (ref "C35") (pin "2") (pinfunction "2_2") (pintype "passive"))
      (node (ref "C36") (pin "1") (pinfunction "1_1") (pintype "passive"))
      (node (ref "C5") (pin "1") (pinfunction "1_1") (pintype "passive"))
      (node (ref "C6") (pin "1") (pinfunction "1_1") (pintype "passive"))
      (node (ref "C7") (pin "1") (pinfunction "1_1") (pintype "passive"))
      (node (ref "C8") (pin "1") (pinfunction "1_1") (pintype "passive"))
      (node (ref "C9") (pin "1") (pinfunction "1_1") (pintype "passive"))
      (node (ref "IC1") (pin "2") (pinfunction "K_2") (pintype "input"))
      (node (ref "IC2") (pin "2") (pinfunction "DGND_2") (pintype "power_in"))
      (node (ref "IC2") (pin "9") (pinfunction "REF_9") (pintype "input"))
      (node (ref "IC6") (pin "2") (pinfunction "K_2") (pintype "input"))
      (node (ref "IC8") (pin "2") (pinfunction "DGND_2") (pintype "power_in"))
      (node (ref "IC8") (pin "9") (pinfunction "REF_9") (pintype "input"))
      (node (ref "J2") (pin "2") (pinfunction "2_2") (pintype "bidirectional"))
      (node (ref "J3") (pin "2") (pinfunction "2_2") (pintype "bidirectional"))
      (node (ref "J6") (pin "2") (pinfunction "2_2") (pintype "bidirectional"))
      (node (ref "J7") (pin "2") (pinfunction "2_2") (pintype "bidirectional"))
      (node (ref "R12") (pin "1") (pinfunction "1_1") (pintype "passive"))
      (node (ref "R18") (pin "1") (pinfunction "1_1") (pintype "passive"))
      (node (ref "R28") (pin "1") (pinfunction "1_1") (pintype "passive"))
      (node (ref "R4") (pin "1") (pinfunction "1_1") (pintype "passive"))
      (node (ref "T1") (pin "2") (pinfunction "S_2") (pintype "passive"))
      (node (ref "T2") (pin "2") (pinfunction "S_2") (pintype "passive"))
    )
    (net (code "30") (name "N11V5A") (class "Default")
      (node (ref "C25") (pin "2") (pinfunction "2_2") (pintype "passive"))
      (node (ref "C27") (pin "2") (pinfunction "2_2") (pintype "passive"))
      (node (ref "C28") (pin "2") (pinfunction "2_2") (pintype "passive"))
      (node (ref "C6") (pin "2") (pinfunction "2_2") (pintype "passive"))
      (node (ref "C8") (pin "2") (pinfunction "2_2") (pintype "passive"))
      (node (ref "C9") (pin "2") (pinfunction "2_2") (pintype "passive"))
      (node (ref "D1") (pin "1") (pinfunction "A_1") (pintype "passive"))
      (node (ref "D2") (pin "1") (pinfunction "A_1") (pintype "passive"))
      (node (ref "D3") (pin "1") (pinfunction "A_1") (pintype "passive"))
      (node (ref "D4") (pin "1") (pinfunction "A_1") (pintype "passive"))
      (node (ref "IC2") (pin "3") (pinfunction "-VS_3") (pintype "power_in"))
      (node (ref "IC2") (pin "6") (pinfunction "~{WR}_6") (pintype "input"))
      (node (ref "IC5") (pin "4") (pinfunction "V-_4") (pintype "power_in"))
      (node (ref "IC8") (pin "3") (pinfunction "-VS_3") (pintype "power_in"))
      (node (ref "IC8") (pin "6") (pinfunction "~{WR}_6") (pintype "input"))
      (node (ref "IC9") (pin "4") (pinfunction "V-_4") (pintype "power_in"))
    )
    (net (code "31") (name "Net-(D1A-COMAC)") (class "Default")
      (node (ref "C10") (pin "2") (pinfunction "2_2") (pintype "passive"))
      (node (ref "C12") (pin "2") (pinfunction "2_2") (pintype "passive"))
      (node (ref "D1") (pin "3") (pinfunction "COMAC_3") (pintype "passive"))
      (node (ref "IC2") (pin "10") (pinfunction "+IN_10") (pintype "input"))
      (node (ref "R3") (pin "2") (pinfunction "2_2") (pintype "passive"))
    )
    (net (code "32") (name "Net-(D2A-COMAC)") (class "Default")
      (node (ref "C12") (pin "1") (pinfunction "1_1") (pintype "passive"))
      (node (ref "C15") (pin "2") (pinfunction "2_2") (pintype "passive"))
      (node (ref "D2") (pin "3") (pinfunction "COMAC_3") (pintype "passive"))
      (node (ref "IC2") (pin "1") (pinfunction "-IN_1") (pintype "input"))
      (node (ref "R11") (pin "2") (pinfunction "2_2") (pintype "passive"))
    )
    (net (code "33") (name "Net-(D3A-COMAC)") (class "Default")
      (node (ref "C29") (pin "2") (pinfunction "2_2") (pintype "passive"))
      (node (ref "C30") (pin "2") (pinfunction "2_2") (pintype "passive"))
      (node (ref "D3") (pin "3") (pinfunction "COMAC_3") (pintype "passive"))
      (node (ref "IC8") (pin "10") (pinfunction "+IN_10") (pintype "input"))
      (node (ref "R17") (pin "2") (pinfunction "2_2") (pintype "passive"))
    )
    (net (code "34") (name "Net-(D4A-COMAC)") (class "Default")
      (node (ref "C30") (pin "1") (pinfunction "1_1") (pintype "passive"))
      (node (ref "C33") (pin "2") (pinfunction "2_2") (pintype "passive"))
      (node (ref "D4") (pin "3") (pinfunction "COMAC_3") (pintype "passive"))
      (node (ref "IC8") (pin "1") (pinfunction "-IN_1") (pintype "input"))
      (node (ref "R25") (pin "2") (pinfunction "2_2") (pintype "passive"))
    )
    (net (code "35") (name "Net-(IC1-A)") (class "Default")
      (node (ref "IC1") (pin "1") (pinfunction "A_1") (pintype "input"))
      (node (ref "R6") (pin "2") (pinfunction "2_2") (pintype "passive"))
    )
    (net (code "36") (name "Net-(IC1-E)") (class "Default")
      (node (ref "IC1") (pin "4") (pinfunction "E_4") (pintype "open_emitter"))
      (node (ref "R5") (pin "2") (pinfunction "2_2") (pintype "passive"))
    )
    (net (code "37") (name "Net-(IC2-OUT)") (class "Default")
      (node (ref "IC2") (pin "7") (pinfunction "OUT_7") (pintype "output"))
      (node (ref "RN1") (pin "1") (pinfunction "1_1") (pintype "passive"))
    )
    (net (code "38") (name "Net-(IC5A-IN+)") (class "Default")
      (node (ref "C13") (pin "2") (pinfunction "2_2") (pintype "passive"))
      (node (ref "IC5") (pin "3") (pinfunction "IN+_3") (pintype "input"))
      (node (ref "R8") (pin "2") (pinfunction "2_2") (pintype "passive"))
      (node (ref "RN2") (pin "1") (pinfunction "1_1") (pintype "passive"))
      (node (ref "RN2") (pin "4") (pinfunction "4_4") (pintype "passive"))
    )
    (net (code "39") (name "Net-(IC5A-IN-)") (class "Default")
      (node (ref "IC5") (pin "2") (pinfunction "IN-_2") (pintype "input"))
      (node (ref "RN1") (pin "2") (pinfunction "2_2") (pintype "passive"))
      (node (ref "RN1") (pin "3") (pinfunction "3_3") (pintype "passive"))
    )
    (net (code "40") (name "Net-(IC5A-OUT)") (class "Default")
      (node (ref "IC5") (pin "1") (pinfunction "OUT_1") (pintype "output"))
      (node (ref "R7") (pin "1") (pinfunction "1_1") (pintype "passive"))
      (node (ref "RN1") (pin "7") (pinfunction "7_7") (pintype "passive"))
      (node (ref "RN2") (pin "7") (pinfunction "7_7") (pintype "passive"))
    )
    (net (code "41") (name "Net-(IC5B-IN+)") (class "Default")
      (node (ref "C22") (pin "2") (pinfunction "2_2") (pintype "passive"))
      (node (ref "IC5") (pin "5") (pinfunction "IN+_5") (pintype "input"))
      (node (ref "R14") (pin "2") (pinfunction "2_2") (pintype "passive"))
    )
    (net (code "42") (name "Net-(IC5B-IN-)") (class "Default")
      (node (ref "IC5") (pin "6") (pinfunction "IN-_6") (pintype "input"))
      (node (ref "RN2") (pin "2") (pinfunction "2_2") (pintype "passive"))
      (node (ref "RN2") (pin "3") (pinfunction "3_3") (pintype "passive"))
    )
    (net (code "43") (name "Net-(IC5B-OUT)") (class "Default")
      (node (ref "IC5") (pin "7") (pinfunction "OUT_7") (pintype "output"))
      (node (ref "R13") (pin "1") (pinfunction "1_1") (pintype "passive"))
      (node (ref "RN2") (pin "6") (pinfunction "6_6") (pintype "passive"))
    )
    (net (code "44") (name "Net-(IC6-A)") (class "Default")
      (node (ref "IC6") (pin "1") (pinfunction "A_1") (pintype "input"))
      (node (ref "R20") (pin "2") (pinfunction "2_2") (pintype "passive"))
    )
    (net (code "45") (name "Net-(IC6-E)") (class "Default")
      (node (ref "IC6") (pin "4") (pinfunction "E_4") (pintype "open_emitter"))
      (node (ref "R19") (pin "2") (pinfunction "2_2") (pintype "passive"))
    )
    (net (code "46") (name "Net-(IC8-OUT)") (class "Default")
      (node (ref "IC8") (pin "7") (pinfunction "OUT_7") (pintype "output"))
      (node (ref "RN3") (pin "1") (pinfunction "1_1") (pintype "passive"))
    )
    (net (code "47") (name "Net-(IC9A-IN+)") (class "Default")
      (node (ref "C31") (pin "2") (pinfunction "2_2") (pintype "passive"))
      (node (ref "IC9") (pin "3") (pinfunction "IN+_3") (pintype "input"))
      (node (ref "R22") (pin "2") (pinfunction "2_2") (pintype "passive"))
      (node (ref "RN4") (pin "1") (pinfunction "1_1") (pintype "passive"))
      (node (ref "RN4") (pin "4") (pinfunction "4_4") (pintype "passive"))
    )
    (net (code "48") (name "Net-(IC9A-IN-)") (class "Default")
      (node (ref "IC9") (pin "2") (pinfunction "IN-_2") (pintype "input"))
      (node (ref "RN3") (pin "2") (pinfunction "2_2") (pintype "passive"))
      (node (ref "RN3") (pin "3") (pinfunction "3_3") (pintype "passive"))
    )
    (net (code "49") (name "Net-(IC9A-OUT)") (class "Default")
      (node (ref "IC9") (pin "1") (pinfunction "OUT_1") (pintype "output"))
      (node (ref "R21") (pin "1") (pinfunction "1_1") (pintype "passive"))
      (node (ref "RN3") (pin "7") (pinfunction "7_7") (pintype "passive"))
      (node (ref "RN4") (pin "7") (pinfunction "7_7") (pintype "passive"))
    )
    (net (code "50") (name "Net-(IC9B-IN+)") (class "Default")
      (node (ref "C36") (pin "2") (pinfunction "2_2") (pintype "passive"))
      (node (ref "IC9") (pin "5") (pinfunction "IN+_5") (pintype "input"))
      (node (ref "R30") (pin "2") (pinfunction "2_2") (pintype "passive"))
    )
    (net (code "51") (name "Net-(IC9B-IN-)") (class "Default")
      (node (ref "IC9") (pin "6") (pinfunction "IN-_6") (pintype "input"))
      (node (ref "RN4") (pin "2") (pinfunction "2_2") (pintype "passive"))
      (node (ref "RN4") (pin "3") (pinfunction "3_3") (pintype "passive"))
    )
    (net (code "52") (name "Net-(IC9B-OUT)") (class "Default")
      (node (ref "IC9") (pin "7") (pinfunction "OUT_7") (pintype "output"))
      (node (ref "R29") (pin "1") (pinfunction "1_1") (pintype "passive"))
      (node (ref "RN4") (pin "6") (pinfunction "6_6") (pintype "passive"))
    )
    (net (code "53") (name "Net-(L1-Pad3)") (class "Default")
      (node (ref "L1") (pin "3") (pinfunction "3_3") (pintype "passive"))
      (node (ref "R10") (pin "1") (pinfunction "1_1") (pintype "passive"))
      (node (ref "R9") (pin "2") (pinfunction "2_2") (pintype "passive"))
    )
    (net (code "54") (name "Net-(L1-Pad4)") (class "Default")
      (node (ref "L1") (pin "4") (pinfunction "4_4") (pintype "passive"))
      (node (ref "R1") (pin "2") (pinfunction "2_2") (pintype "passive"))
      (node (ref "R2") (pin "1") (pinfunction "1_1") (pintype "passive"))
    )
    (net (code "55") (name "Net-(L2-Pad3)") (class "Default")
      (node (ref "L2") (pin "3") (pinfunction "3_3") (pintype "passive"))
      (node (ref "R23") (pin "2") (pinfunction "2_2") (pintype "passive"))
      (node (ref "R24") (pin "1") (pinfunction "1_1") (pintype "passive"))
    )
    (net (code "56") (name "Net-(L2-Pad4)") (class "Default")
      (node (ref "L2") (pin "4") (pinfunction "4_4") (pintype "passive"))
      (node (ref "R15") (pin "2") (pinfunction "2_2") (pintype "passive"))
      (node (ref "R16") (pin "1") (pinfunction "1_1") (pintype "passive"))
    )
    (net (code "57") (name "Net-(LD2-C)") (class "Default")
      (node (ref "LD2") (pin "1") (pinfunction "C_1") (pintype "passive"))
      (node (ref "T1") (pin "3") (pinfunction "D_3") (pintype "passive"))
    )
    (net (code "58") (name "Net-(LD3-C)") (class "Default")
      (node (ref "LD3") (pin "1") (pinfunction "C_1") (pintype "passive"))
      (node (ref "T2") (pin "3") (pinfunction "D_3") (pintype "passive"))
    )
    (net (code "59") (name "Net-(R2-Pad2)") (class "Default")
      (node (ref "R2") (pin "2") (pinfunction "2_2") (pintype "passive"))
      (node (ref "R3") (pin "1") (pinfunction "1_1") (pintype "passive"))
      (node (ref "R4") (pin "2") (pinfunction "2_2") (pintype "passive"))
    )
    (net (code "60") (name "Net-(R10-Pad2)") (class "Default")
      (node (ref "R10") (pin "2") (pinfunction "2_2") (pintype "passive"))
      (node (ref "R11") (pin "1") (pinfunction "1_1") (pintype "passive"))
      (node (ref "R12") (pin "2") (pinfunction "2_2") (pintype "passive"))
    )
    (net (code "61") (name "Net-(R16-Pad2)") (class "Default")
      (node (ref "R16") (pin "2") (pinfunction "2_2") (pintype "passive"))
      (node (ref "R17") (pin "1") (pinfunction "1_1") (pintype "passive"))
      (node (ref "R18") (pin "2") (pinfunction "2_2") (pintype "passive"))
    )
    (net (code "62") (name "Net-(R24-Pad2)") (class "Default")
      (node (ref "R24") (pin "2") (pinfunction "2_2") (pintype "passive"))
      (node (ref "R25") (pin "1") (pinfunction "1_1") (pintype "passive"))
      (node (ref "R28") (pin "2") (pinfunction "2_2") (pintype "passive"))
    )
    (net (code "63") (name "Net-(RN1-Pad4)") (class "Default")
      (node (ref "RN1") (pin "4") (pinfunction "4_4") (pintype "passive"))
      (node (ref "RN1") (pin "8") (pinfunction "8_8") (pintype "passive"))
    )
    (net (code "64") (name "Net-(RN1-Pad5)") (class "Default")
      (node (ref "RN1") (pin "5") (pinfunction "5_5") (pintype "passive"))
      (node (ref "RN1") (pin "6") (pinfunction "6_6") (pintype "passive"))
    )
    (net (code "65") (name "Net-(RN3-Pad4)") (class "Default")
      (node (ref "RN3") (pin "4") (pinfunction "4_4") (pintype "passive"))
      (node (ref "RN3") (pin "8") (pinfunction "8_8") (pintype "passive"))
    )
    (net (code "66") (name "Net-(RN3-Pad5)") (class "Default")
      (node (ref "RN3") (pin "5") (pinfunction "5_5") (pintype "passive"))
      (node (ref "RN3") (pin "6") (pinfunction "6_6") (pintype "passive"))
    )
    (net (code "67") (name "P3V3") (class "Default")
      (node (ref "LD2") (pin "2") (pinfunction "A_2") (pintype "passive"))
      (node (ref "LD3") (pin "2") (pinfunction "A_2") (pintype "passive"))
      (node (ref "R52") (pin "1") (pinfunction "1_1") (pintype "passive"))
      (node (ref "R53") (pin "1") (pinfunction "1_1") (pintype "passive"))
    )
    (net (code "68") (name "P11V5A") (class "Default")
      (node (ref "C1") (pin "1") (pinfunction "1_1") (pintype "passive"))
      (node (ref "C23") (pin "1") (pinfunction "1_1") (pintype "passive"))
      (node (ref "C24") (pin "2") (pinfunction "2_2") (pintype "passive"))
      (node (ref "C26") (pin "2") (pinfunction "2_2") (pintype "passive"))
      (node (ref "C5") (pin "2") (pinfunction "2_2") (pintype "passive"))
      (node (ref "C7") (pin "2") (pinfunction "2_2") (pintype "passive"))
      (node (ref "D1") (pin "2") (pinfunction "C_2") (pintype "passive"))
      (node (ref "D2") (pin "2") (pinfunction "C_2") (pintype "passive"))
      (node (ref "D3") (pin "2") (pinfunction "C_2") (pintype "passive"))
      (node (ref "D4") (pin "2") (pinfunction "C_2") (pintype "passive"))
      (node (ref "IC2") (pin "8") (pinfunction "+VS_8") (pintype "power_in"))
      (node (ref "IC5") (pin "8") (pinfunction "V+_8") (pintype "power_in"))
      (node (ref "IC8") (pin "8") (pinfunction "+VS_8") (pintype "power_in"))
      (node (ref "IC9") (pin "8") (pinfunction "V+_8") (pintype "power_in"))
    )
    (net (code "69") (name "REF_P1V5") (class "Default")
      (node (ref "R14") (pin "1") (pinfunction "1_1") (pintype "passive"))
      (node (ref "R30") (pin "1") (pinfunction "1_1") (pintype "passive"))
    )
    (net (code "70") (name "REF_P1V25") (class "Default")
      (node (ref "R22") (pin "1") (pinfunction "1_1") (pintype "passive"))
      (node (ref "R8") (pin "1") (pinfunction "1_1") (pintype "passive"))
      (node (ref "RN2") (pin "5") (pinfunction "5_5") (pintype "passive"))
      (node (ref "RN2") (pin "8") (pinfunction "8_8") (pintype "passive"))
      (node (ref "RN4") (pin "5") (pinfunction "5_5") (pintype "passive"))
      (node (ref "RN4") (pin "8") (pinfunction "8_8") (pintype "passive"))
    )
  )
)
